# B4_FM__Z_SOLAR_PANEL.net
KiCad netlist of a schematic drawn in EAGLE
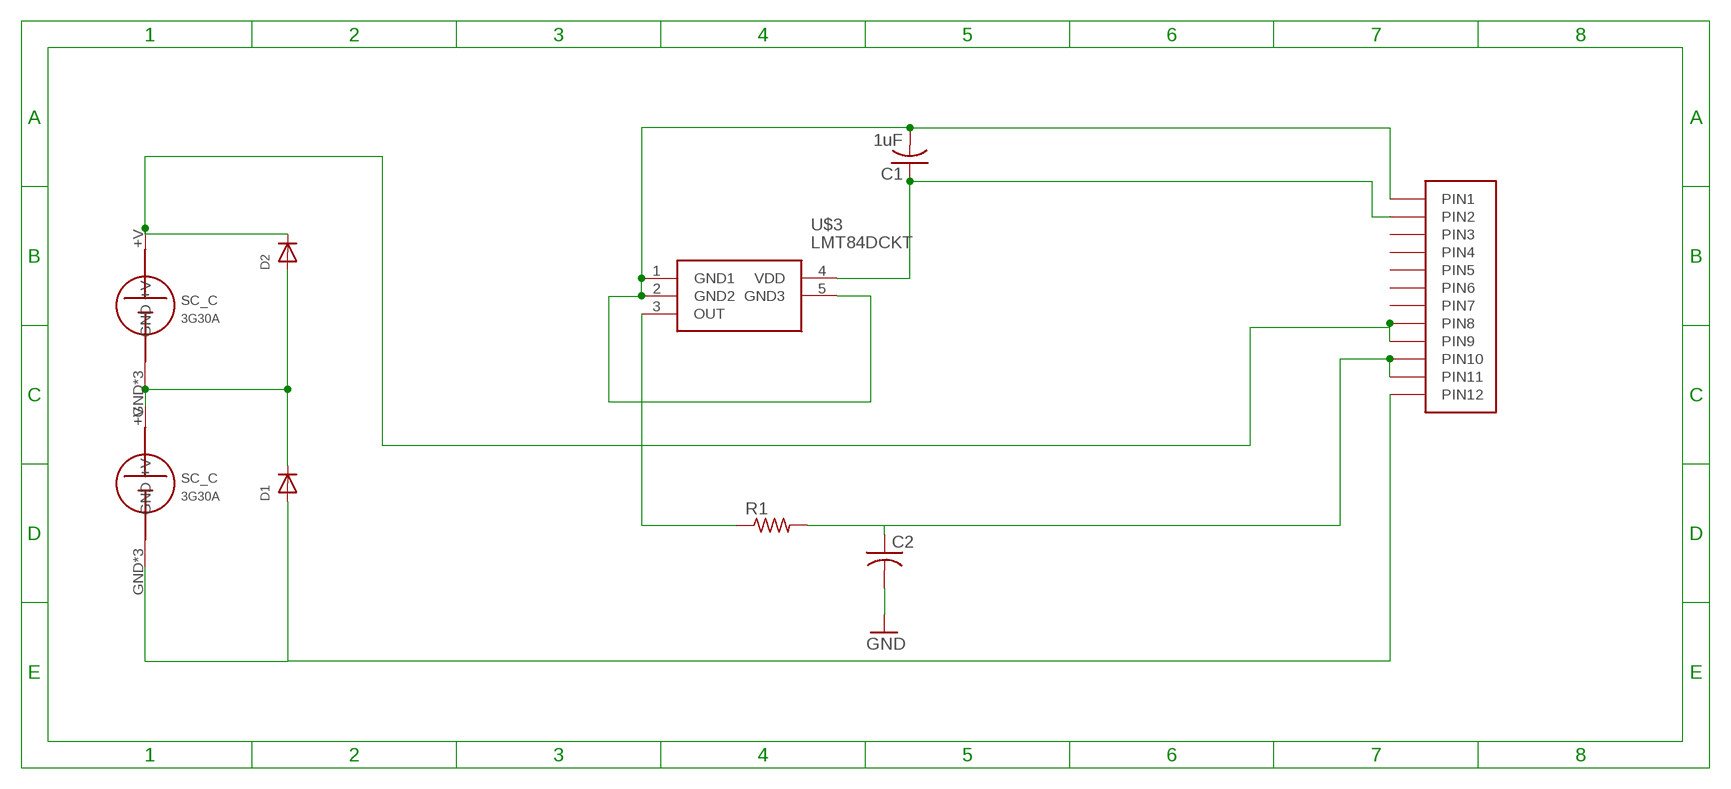
[diagram p0: schematic, sheet 1]

(export (version "E")
  (design (tool "Eeschema 10.0.6"))
  (components
    (comp (ref "C1")
      (value "1uF")
      (footprint "eagle-import:C2012")
      (libsource (lib "eagle-import") (part "C-USC2012"))
    )
    (comp (ref "C2")
      (value "C-USC2012")
      (footprint "eagle-import:C2012")
      (libsource (lib "eagle-import") (part "C-USC2012"))
    )
    (comp (ref "D1")
      (value "DIODE_SOD-123FL")
      (footprint "eagle-import:SOD-123FL")
      (libsource (lib "eagle-import") (part "DIODE_SOD-123FL"))
    )
    (comp (ref "D2")
      (value "DIODE_SOD-123FL")
      (footprint "eagle-import:SOD-123FL")
      (libsource (lib "eagle-import") (part "DIODE_SOD-123FL"))
    )
    (comp (ref "R1")
      (value "R-US_R0402")
      (footprint "eagle-import:R0402")
      (libsource (lib "eagle-import") (part "R-US_R0402"))
    )
    (comp (ref "U$1")
      (value "HEADER12PIN")
      (footprint "eagle-import:HEADER12PIN")
      (libsource (lib "eagle-import") (part "HEADER12PIN"))
    )
    (comp (ref "U$3")
      (value "LMT84DCKT")
      (footprint "eagle-import:SOT65P210X110-5N")
      (fields (field (name "RS_PART_NUMBER") "8115860"))
      (libsource (lib "eagle-import") (part "LMT84DCKT"))
    )
    (comp (ref "U$4")
      (value "SC_C")
      (footprint "eagle-import:SC_C")
      (libsource (lib "eagle-import") (part "SC_C"))
    )
    (comp (ref "U$5")
      (value "SC_C")
      (footprint "eagle-import:SC_C")
      (libsource (lib "eagle-import") (part "SC_C"))
    )
  )
  (nets
    (net (code "1") (name "GND") (class "Default")
      (node (ref "C1") (pin "2") (pinfunction "2_2") (pintype "passive"))
      (node (ref "C2") (pin "2") (pinfunction "2_2") (pintype "passive"))
      (node (ref "D1") (pin "A") (pinfunction "A_A") (pintype "passive"))
      (node (ref "U$1") (pin "P1") (pinfunction "PIN1_P1") (pintype "bidirectional"))
      (node (ref "U$1") (pin "P12") (pinfunction "PIN12_P12") (pintype "bidirectional"))
      (node (ref "U$3") (pin "1") (pinfunction "GND1_1") (pintype "power_in"))
      (node (ref "U$3") (pin "2") (pinfunction "GND2_2") (pintype "power_in"))
      (node (ref "U$3") (pin "5") (pinfunction "GND3_5") (pintype "power_in"))
      (node (ref "U$5") (pin "GND") (pinfunction "GND_GND") (pintype "bidirectional"))
      (node (ref "U$5") (pin "GND1") (pinfunction "GND_GND1") (pintype "bidirectional"))
      (node (ref "U$5") (pin "GND2") (pinfunction "GND_GND2") (pintype "bidirectional"))
    )
    (net (code "2") (name "Net-(D1-PadC)") (class "Default")
      (node (ref "D1") (pin "C") (pinfunction "C_C") (pintype "passive"))
      (node (ref "D2") (pin "A") (pinfunction "A_A") (pintype "passive"))
      (node (ref "U$4") (pin "GND") (pinfunction "GND_GND") (pintype "bidirectional"))
      (node (ref "U$4") (pin "GND1") (pinfunction "GND_GND1") (pintype "bidirectional"))
      (node (ref "U$4") (pin "GND2") (pinfunction "GND_GND2") (pintype "bidirectional"))
      (node (ref "U$5") (pin "+V") (pinfunction "+V_+V") (pintype "bidirectional"))
    )
    (net (code "3") (name "Net-(U$1-PIN2)") (class "Default")
      (node (ref "C1") (pin "1") (pinfunction "1_1") (pintype "passive"))
      (node (ref "U$1") (pin "P2") (pinfunction "PIN2_P2") (pintype "bidirectional"))
      (node (ref "U$3") (pin "4") (pinfunction "VDD_4") (pintype "power_in"))
    )
    (net (code "4") (name "Net-(U$1-PIN8)") (class "Default")
      (node (ref "D2") (pin "C") (pinfunction "C_C") (pintype "passive"))
      (node (ref "U$1") (pin "P8") (pinfunction "PIN8_P8") (pintype "bidirectional"))
      (node (ref "U$1") (pin "P9") (pinfunction "PIN9_P9") (pintype "bidirectional"))
      (node (ref "U$4") (pin "+V") (pinfunction "+V_+V") (pintype "bidirectional"))
    )
    (net (code "5") (name "Net-(U$1-PIN10)") (class "Default")
      (node (ref "C2") (pin "1") (pinfunction "1_1") (pintype "passive"))
      (node (ref "R1") (pin "2") (pinfunction "2_2") (pintype "passive"))
      (node (ref "U$1") (pin "P10") (pinfunction "PIN10_P10") (pintype "bidirectional"))
      (node (ref "U$1") (pin "P11") (pinfunction "PIN11_P11") (pintype "bidirectional"))
    )
    (net (code "6") (name "Net-(U$3-OUT)") (class "Default")
      (node (ref "R1") (pin "1") (pinfunction "1_1") (pintype "passive"))
      (node (ref "U$3") (pin "3") (pinfunction "OUT_3") (pintype "output"))
    )
    (net (code "7") (name "unconnected-(U$1-PIN3-PadP3)") (class "Default")
      (node (ref "U$1") (pin "P3") (pinfunction "PIN3_P3") (pintype "bidirectional"))
    )
    (net (code "8") (name "unconnected-(U$1-PIN4-PadP4)") (class "Default")
      (node (ref "U$1") (pin "P4") (pinfunction "PIN4_P4") (pintype "bidirectional"))
    )
    (net (code "9") (name "unconnected-(U$1-PIN5-PadP5)") (class "Default")
      (node (ref "U$1") (pin "P5") (pinfunction "PIN5_P5") (pintype "bidirectional"))
    )
    (net (code "10") (name "unconnected-(U$1-PIN6-PadP6)") (class "Default")
      (node (ref "U$1") (pin "P6") (pinfunction "PIN6_P6") (pintype "bidirectional"))
    )
    (net (code "11") (name "unconnected-(U$1-PIN7-PadP7)") (class "Default")
      (node (ref "U$1") (pin "P7") (pinfunction "PIN7_P7") (pintype "bidirectional"))
    )
  )
)
